# Inputs.net
KiCad netlist of a schematic drawn in Altium Designer
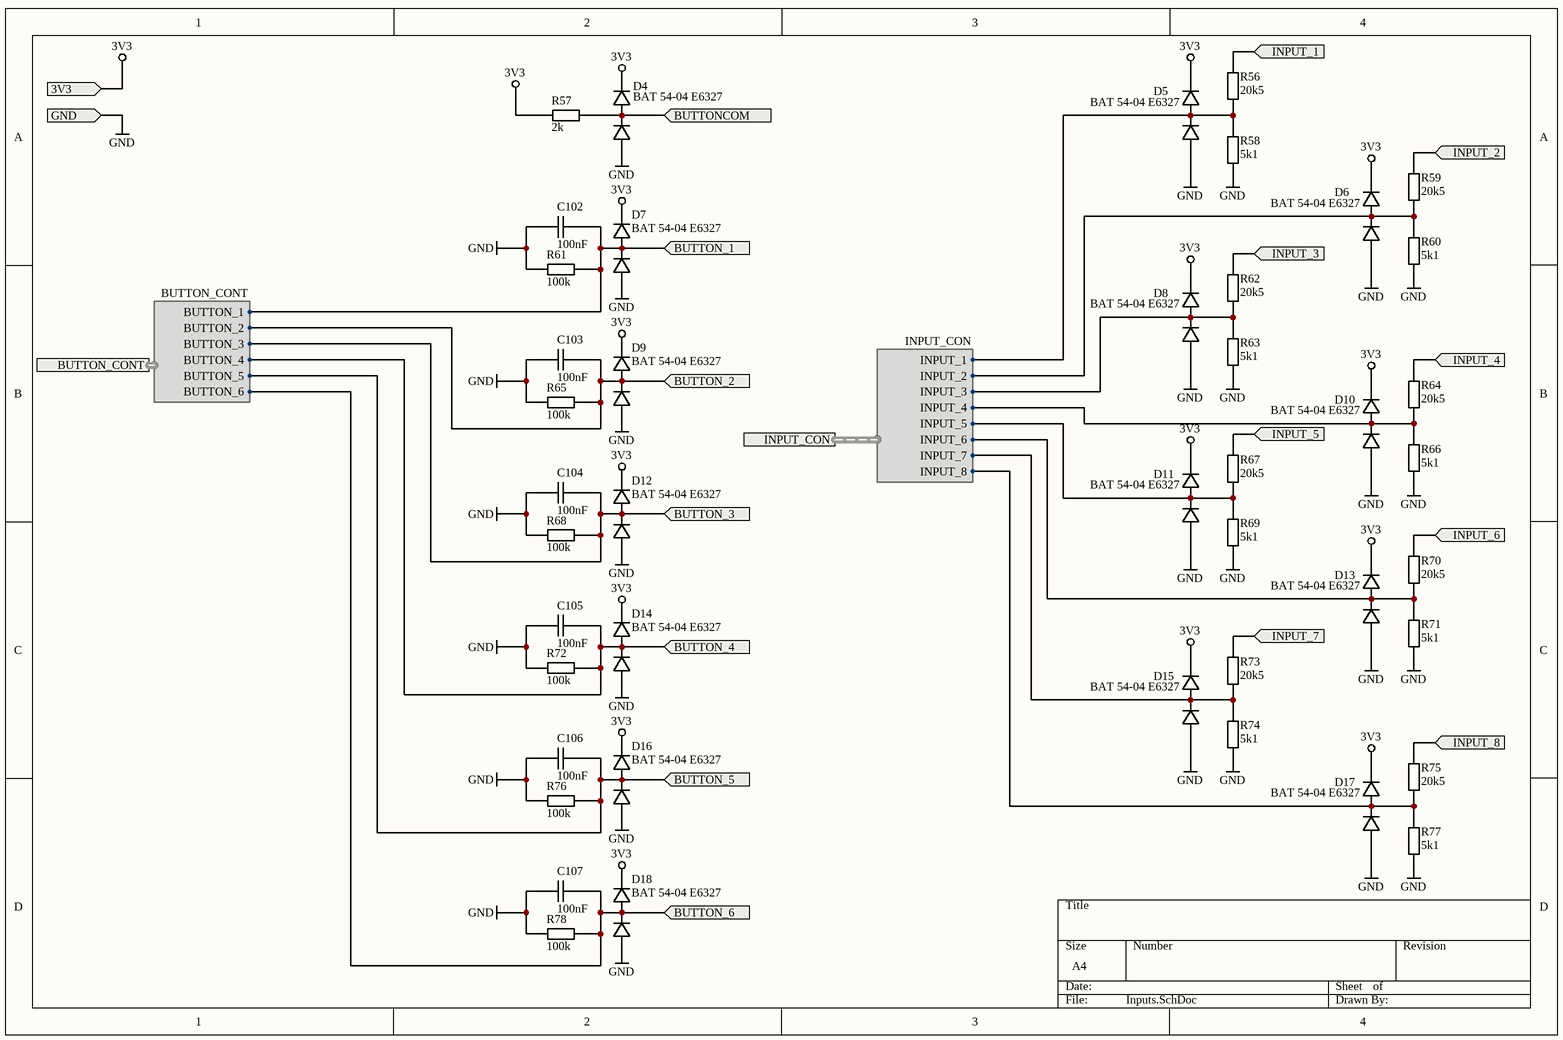
[diagram p0: Inputs.SchDoc]

(export (version "E")
  (design (tool "Eeschema 10.0.6"))
  (components
    (comp (ref "C102")
      (value "100nF")
      (footprint "C_0402")
      (description "100nF 10V 0402 X7R")
      (libsource (lib "SchematicLibrary") (part "C0402C104J8RACAUTO"))
    )
    (comp (ref "C103")
      (value "100nF")
      (footprint "C_0402")
      (description "100nF 10V 0402 X7R")
      (libsource (lib "SchematicLibrary") (part "C0402C104J8RACAUTO"))
    )
    (comp (ref "C104")
      (value "100nF")
      (footprint "C_0402")
      (description "100nF 10V 0402 X7R")
      (libsource (lib "SchematicLibrary") (part "C0402C104J8RACAUTO"))
    )
    (comp (ref "C105")
      (value "100nF")
      (footprint "C_0402")
      (description "100nF 10V 0402 X7R")
      (libsource (lib "SchematicLibrary") (part "C0402C104J8RACAUTO"))
    )
    (comp (ref "C106")
      (value "100nF")
      (footprint "C_0402")
      (description "100nF 10V 0402 X7R")
      (libsource (lib "SchematicLibrary") (part "C0402C104J8RACAUTO"))
    )
    (comp (ref "C107")
      (value "100nF")
      (footprint "C_0402")
      (description "100nF 10V 0402 X7R")
      (libsource (lib "SchematicLibrary") (part "C0402C104J8RACAUTO"))
    )
    (comp (ref "D4")
      (value "BAT 54-04 E6327")
      (footprint "SOT95P240X110-3N")
      (description "Clamping Diode")
      (libsource (lib "SchematicLibrary") (part "BAT 54-04 E6327"))
    )
    (comp (ref "D5")
      (value "BAT 54-04 E6327")
      (footprint "SOT95P240X110-3N")
      (description "Clamping Diode")
      (libsource (lib "SchematicLibrary") (part "BAT 54-04 E6327"))
    )
    (comp (ref "D6")
      (value "BAT 54-04 E6327")
      (footprint "SOT95P240X110-3N")
      (description "Clamping Diode")
      (libsource (lib "SchematicLibrary") (part "BAT 54-04 E6327"))
    )
    (comp (ref "D7")
      (value "BAT 54-04 E6327")
      (footprint "SOT95P240X110-3N")
      (description "Clamping Diode")
      (libsource (lib "SchematicLibrary") (part "BAT 54-04 E6327"))
    )
    (comp (ref "D8")
      (value "BAT 54-04 E6327")
      (footprint "SOT95P240X110-3N")
      (description "Clamping Diode")
      (libsource (lib "SchematicLibrary") (part "BAT 54-04 E6327"))
    )
    (comp (ref "D9")
      (value "BAT 54-04 E6327")
      (footprint "SOT95P240X110-3N")
      (description "Clamping Diode")
      (libsource (lib "SchematicLibrary") (part "BAT 54-04 E6327"))
    )
    (comp (ref "D10")
      (value "BAT 54-04 E6327")
      (footprint "SOT95P240X110-3N")
      (description "Clamping Diode")
      (libsource (lib "SchematicLibrary") (part "BAT 54-04 E6327"))
    )
    (comp (ref "D11")
      (value "BAT 54-04 E6327")
      (footprint "SOT95P240X110-3N")
      (description "Clamping Diode")
      (libsource (lib "SchematicLibrary") (part "BAT 54-04 E6327"))
    )
    (comp (ref "D12")
      (value "BAT 54-04 E6327")
      (footprint "SOT95P240X110-3N")
      (description "Clamping Diode")
      (libsource (lib "SchematicLibrary") (part "BAT 54-04 E6327"))
    )
    (comp (ref "D13")
      (value "BAT 54-04 E6327")
      (footprint "SOT95P240X110-3N")
      (description "Clamping Diode")
      (libsource (lib "SchematicLibrary") (part "BAT 54-04 E6327"))
    )
    (comp (ref "D14")
      (value "BAT 54-04 E6327")
      (footprint "SOT95P240X110-3N")
      (description "Clamping Diode")
      (libsource (lib "SchematicLibrary") (part "BAT 54-04 E6327"))
    )
    (comp (ref "D15")
      (value "BAT 54-04 E6327")
      (footprint "SOT95P240X110-3N")
      (description "Clamping Diode")
      (libsource (lib "SchematicLibrary") (part "BAT 54-04 E6327"))
    )
    (comp (ref "D16")
      (value "BAT 54-04 E6327")
      (footprint "SOT95P240X110-3N")
      (description "Clamping Diode")
      (libsource (lib "SchematicLibrary") (part "BAT 54-04 E6327"))
    )
    (comp (ref "D17")
      (value "BAT 54-04 E6327")
      (footprint "SOT95P240X110-3N")
      (description "Clamping Diode")
      (libsource (lib "SchematicLibrary") (part "BAT 54-04 E6327"))
    )
    (comp (ref "D18")
      (value "BAT 54-04 E6327")
      (footprint "SOT95P240X110-3N")
      (description "Clamping Diode")
      (libsource (lib "SchematicLibrary") (part "BAT 54-04 E6327"))
    )
    (comp (ref "R56")
      (value "20k5")
      (footprint "R_0402")
      (description "20k5 1% 100mW")
      (libsource (lib "SchematicLibrary") (part "ERJ2RKF2052X"))
    )
    (comp (ref "R57")
      (value "2k")
      (footprint "R_0402")
      (description "2k 1% 62.5mW")
      (libsource (lib "SchematicLibrary") (part "AC0402FR-072KL"))
    )
    (comp (ref "R58")
      (value "5k1")
      (footprint "R_0402")
      (description "5k1 1% 100mW")
      (libsource (lib "SchematicLibrary") (part "MP000528"))
    )
    (comp (ref "R59")
      (value "20k5")
      (footprint "R_0402")
      (description "20k5 1% 100mW")
      (libsource (lib "SchematicLibrary") (part "ERJ2RKF2052X"))
    )
    (comp (ref "R60")
      (value "5k1")
      (footprint "R_0402")
      (description "5k1 1% 100mW")
      (libsource (lib "SchematicLibrary") (part "MP000528"))
    )
    (comp (ref "R61")
      (value "100k")
      (footprint "R_0402")
      (description "100k 5% 62.5mW")
      (libsource (lib "SchematicLibrary") (part "CRCW0402100KJNED"))
    )
    (comp (ref "R62")
      (value "20k5")
      (footprint "R_0402")
      (description "20k5 1% 100mW")
      (libsource (lib "SchematicLibrary") (part "ERJ2RKF2052X"))
    )
    (comp (ref "R63")
      (value "5k1")
      (footprint "R_0402")
      (description "5k1 1% 100mW")
      (libsource (lib "SchematicLibrary") (part "MP000528"))
    )
    (comp (ref "R64")
      (value "20k5")
      (footprint "R_0402")
      (description "20k5 1% 100mW")
      (libsource (lib "SchematicLibrary") (part "ERJ2RKF2052X"))
    )
    (comp (ref "R65")
      (value "100k")
      (footprint "R_0402")
      (description "100k 5% 62.5mW")
      (libsource (lib "SchematicLibrary") (part "CRCW0402100KJNED"))
    )
    (comp (ref "R66")
      (value "5k1")
      (footprint "R_0402")
      (description "5k1 1% 100mW")
      (libsource (lib "SchematicLibrary") (part "MP000528"))
    )
    (comp (ref "R67")
      (value "20k5")
      (footprint "R_0402")
      (description "20k5 1% 100mW")
      (libsource (lib "SchematicLibrary") (part "ERJ2RKF2052X"))
    )
    (comp (ref "R68")
      (value "100k")
      (footprint "R_0402")
      (description "100k 5% 62.5mW")
      (libsource (lib "SchematicLibrary") (part "CRCW0402100KJNED"))
    )
    (comp (ref "R69")
      (value "5k1")
      (footprint "R_0402")
      (description "5k1 1% 100mW")
      (libsource (lib "SchematicLibrary") (part "MP000528"))
    )
    (comp (ref "R70")
      (value "20k5")
      (footprint "R_0402")
      (description "20k5 1% 100mW")
      (libsource (lib "SchematicLibrary") (part "ERJ2RKF2052X"))
    )
    (comp (ref "R71")
      (value "5k1")
      (footprint "R_0402")
      (description "5k1 1% 100mW")
      (libsource (lib "SchematicLibrary") (part "MP000528"))
    )
    (comp (ref "R72")
      (value "100k")
      (footprint "R_0402")
      (description "100k 5% 62.5mW")
      (libsource (lib "SchematicLibrary") (part "CRCW0402100KJNED"))
    )
    (comp (ref "R73")
      (value "20k5")
      (footprint "R_0402")
      (description "20k5 1% 100mW")
      (libsource (lib "SchematicLibrary") (part "ERJ2RKF2052X"))
    )
    (comp (ref "R74")
      (value "5k1")
      (footprint "R_0402")
      (description "5k1 1% 100mW")
      (libsource (lib "SchematicLibrary") (part "MP000528"))
    )
    (comp (ref "R75")
      (value "20k5")
      (footprint "R_0402")
      (description "20k5 1% 100mW")
      (libsource (lib "SchematicLibrary") (part "ERJ2RKF2052X"))
    )
    (comp (ref "R76")
      (value "100k")
      (footprint "R_0402")
      (description "100k 5% 62.5mW")
      (libsource (lib "SchematicLibrary") (part "CRCW0402100KJNED"))
    )
    (comp (ref "R77")
      (value "5k1")
      (footprint "R_0402")
      (description "5k1 1% 100mW")
      (libsource (lib "SchematicLibrary") (part "MP000528"))
    )
    (comp (ref "R78")
      (value "100k")
      (footprint "R_0402")
      (description "100k 5% 62.5mW")
      (libsource (lib "SchematicLibrary") (part "CRCW0402100KJNED"))
    )
  )
  (nets
    (net (code "3") (name "/BUTTONCOM") (class "Default")
      (node (ref "D4") (pin "3") (pinfunction "3_3") (pintype "passive"))
      (node (ref "R57") (pin "2") (pinfunction "2_2") (pintype "passive"))
    )
    (net (code "4") (name "/BUTTON_1") (class "Default")
      (node (ref "C102") (pin "2") (pinfunction "2_2") (pintype "passive"))
      (node (ref "D7") (pin "3") (pinfunction "3_3") (pintype "passive"))
      (node (ref "R61") (pin "2") (pinfunction "2_2") (pintype "passive"))
    )
    (net (code "5") (name "/BUTTON_2") (class "Default")
      (node (ref "C103") (pin "2") (pinfunction "2_2") (pintype "passive"))
      (node (ref "D9") (pin "3") (pinfunction "3_3") (pintype "passive"))
      (node (ref "R65") (pin "2") (pinfunction "2_2") (pintype "passive"))
    )
    (net (code "6") (name "/BUTTON_3") (class "Default")
      (node (ref "C104") (pin "2") (pinfunction "2_2") (pintype "passive"))
      (node (ref "D12") (pin "3") (pinfunction "3_3") (pintype "passive"))
      (node (ref "R68") (pin "2") (pinfunction "2_2") (pintype "passive"))
    )
    (net (code "7") (name "/BUTTON_4") (class "Default")
      (node (ref "C105") (pin "2") (pinfunction "2_2") (pintype "passive"))
      (node (ref "D14") (pin "3") (pinfunction "3_3") (pintype "passive"))
      (node (ref "R72") (pin "2") (pinfunction "2_2") (pintype "passive"))
    )
    (net (code "8") (name "/BUTTON_5") (class "Default")
      (node (ref "C106") (pin "2") (pinfunction "2_2") (pintype "passive"))
      (node (ref "D16") (pin "3") (pinfunction "3_3") (pintype "passive"))
      (node (ref "R76") (pin "2") (pinfunction "2_2") (pintype "passive"))
    )
    (net (code "9") (name "/BUTTON_6") (class "Default")
      (node (ref "C107") (pin "2") (pinfunction "2_2") (pintype "passive"))
      (node (ref "D18") (pin "3") (pinfunction "3_3") (pintype "passive"))
      (node (ref "R78") (pin "2") (pinfunction "2_2") (pintype "passive"))
    )
    (net (code "10") (name "/INPUT_1") (class "Default")
      (node (ref "R56") (pin "2") (pinfunction "2_2") (pintype "passive"))
    )
    (net (code "11") (name "/INPUT_2") (class "Default")
      (node (ref "R59") (pin "2") (pinfunction "2_2") (pintype "passive"))
    )
    (net (code "12") (name "/INPUT_3") (class "Default")
      (node (ref "R62") (pin "2") (pinfunction "2_2") (pintype "passive"))
    )
    (net (code "13") (name "/INPUT_4") (class "Default")
      (node (ref "R64") (pin "2") (pinfunction "2_2") (pintype "passive"))
    )
    (net (code "14") (name "/INPUT_5") (class "Default")
      (node (ref "R67") (pin "2") (pinfunction "2_2") (pintype "passive"))
    )
    (net (code "15") (name "/INPUT_6") (class "Default")
      (node (ref "R70") (pin "2") (pinfunction "2_2") (pintype "passive"))
    )
    (net (code "16") (name "/INPUT_7") (class "Default")
      (node (ref "R73") (pin "2") (pinfunction "2_2") (pintype "passive"))
    )
    (net (code "17") (name "/INPUT_8") (class "Default")
      (node (ref "R75") (pin "2") (pinfunction "2_2") (pintype "passive"))
    )
    (net (code "20") (name "3V3") (class "Default")
      (node (ref "D10") (pin "2") (pinfunction "2_2") (pintype "passive"))
      (node (ref "D11") (pin "2") (pinfunction "2_2") (pintype "passive"))
      (node (ref "D12") (pin "2") (pinfunction "2_2") (pintype "passive"))
      (node (ref "D13") (pin "2") (pinfunction "2_2") (pintype "passive"))
      (node (ref "D14") (pin "2") (pinfunction "2_2") (pintype "passive"))
      (node (ref "D15") (pin "2") (pinfunction "2_2") (pintype "passive"))
      (node (ref "D16") (pin "2") (pinfunction "2_2") (pintype "passive"))
      (node (ref "D17") (pin "2") (pinfunction "2_2") (pintype "passive"))
      (node (ref "D18") (pin "2") (pinfunction "2_2") (pintype "passive"))
      (node (ref "D4") (pin "2") (pinfunction "2_2") (pintype "passive"))
      (node (ref "D5") (pin "2") (pinfunction "2_2") (pintype "passive"))
      (node (ref "D6") (pin "2") (pinfunction "2_2") (pintype "passive"))
      (node (ref "D7") (pin "2") (pinfunction "2_2") (pintype "passive"))
      (node (ref "D8") (pin "2") (pinfunction "2_2") (pintype "passive"))
      (node (ref "D9") (pin "2") (pinfunction "2_2") (pintype "passive"))
      (node (ref "R57") (pin "1") (pinfunction "1_1") (pintype "passive"))
    )
    (net (code "21") (name "GND") (class "Default")
      (node (ref "C102") (pin "1") (pinfunction "1_1") (pintype "passive"))
      (node (ref "C103") (pin "1") (pinfunction "1_1") (pintype "passive"))
      (node (ref "C104") (pin "1") (pinfunction "1_1") (pintype "passive"))
      (node (ref "C105") (pin "1") (pinfunction "1_1") (pintype "passive"))
      (node (ref "C106") (pin "1") (pinfunction "1_1") (pintype "passive"))
      (node (ref "C107") (pin "1") (pinfunction "1_1") (pintype "passive"))
      (node (ref "D10") (pin "1") (pinfunction "1_1") (pintype "passive"))
      (node (ref "D11") (pin "1") (pinfunction "1_1") (pintype "passive"))
      (node (ref "D12") (pin "1") (pinfunction "1_1") (pintype "passive"))
      (node (ref "D13") (pin "1") (pinfunction "1_1") (pintype "passive"))
      (node (ref "D14") (pin "1") (pinfunction "1_1") (pintype "passive"))
      (node (ref "D15") (pin "1") (pinfunction "1_1") (pintype "passive"))
      (node (ref "D16") (pin "1") (pinfunction "1_1") (pintype "passive"))
      (node (ref "D17") (pin "1") (pinfunction "1_1") (pintype "passive"))
      (node (ref "D18") (pin "1") (pinfunction "1_1") (pintype "passive"))
      (node (ref "D4") (pin "1") (pinfunction "1_1") (pintype "passive"))
      (node (ref "D5") (pin "1") (pinfunction "1_1") (pintype "passive"))
      (node (ref "D6") (pin "1") (pinfunction "1_1") (pintype "passive"))
      (node (ref "D7") (pin "1") (pinfunction "1_1") (pintype "passive"))
      (node (ref "D8") (pin "1") (pinfunction "1_1") (pintype "passive"))
      (node (ref "D9") (pin "1") (pinfunction "1_1") (pintype "passive"))
      (node (ref "R58") (pin "1") (pinfunction "1_1") (pintype "passive"))
      (node (ref "R60") (pin "1") (pinfunction "1_1") (pintype "passive"))
      (node (ref "R61") (pin "1") (pinfunction "1_1") (pintype "passive"))
      (node (ref "R63") (pin "1") (pinfunction "1_1") (pintype "passive"))
      (node (ref "R65") (pin "1") (pinfunction "1_1") (pintype "passive"))
      (node (ref "R66") (pin "1") (pinfunction "1_1") (pintype "passive"))
      (node (ref "R68") (pin "1") (pinfunction "1_1") (pintype "passive"))
      (node (ref "R69") (pin "1") (pinfunction "1_1") (pintype "passive"))
      (node (ref "R71") (pin "1") (pinfunction "1_1") (pintype "passive"))
      (node (ref "R72") (pin "1") (pinfunction "1_1") (pintype "passive"))
      (node (ref "R74") (pin "1") (pinfunction "1_1") (pintype "passive"))
      (node (ref "R76") (pin "1") (pinfunction "1_1") (pintype "passive"))
      (node (ref "R77") (pin "1") (pinfunction "1_1") (pintype "passive"))
      (node (ref "R78") (pin "1") (pinfunction "1_1") (pintype "passive"))
    )
    (net (code "22") (name "Net-(D5-Pad3)") (class "Default")
      (node (ref "D5") (pin "3") (pinfunction "3_3") (pintype "passive"))
      (node (ref "R56") (pin "1") (pinfunction "1_1") (pintype "passive"))
      (node (ref "R58") (pin "2") (pinfunction "2_2") (pintype "passive"))
    )
    (net (code "23") (name "Net-(D6-Pad3)") (class "Default")
      (node (ref "D6") (pin "3") (pinfunction "3_3") (pintype "passive"))
      (node (ref "R59") (pin "1") (pinfunction "1_1") (pintype "passive"))
      (node (ref "R60") (pin "2") (pinfunction "2_2") (pintype "passive"))
    )
    (net (code "24") (name "Net-(D8-Pad3)") (class "Default")
      (node (ref "D8") (pin "3") (pinfunction "3_3") (pintype "passive"))
      (node (ref "R62") (pin "1") (pinfunction "1_1") (pintype "passive"))
      (node (ref "R63") (pin "2") (pinfunction "2_2") (pintype "passive"))
    )
    (net (code "25") (name "Net-(D10-Pad3)") (class "Default")
      (node (ref "D10") (pin "3") (pinfunction "3_3") (pintype "passive"))
      (node (ref "R64") (pin "1") (pinfunction "1_1") (pintype "passive"))
      (node (ref "R66") (pin "2") (pinfunction "2_2") (pintype "passive"))
    )
    (net (code "26") (name "Net-(D11-Pad3)") (class "Default")
      (node (ref "D11") (pin "3") (pinfunction "3_3") (pintype "passive"))
      (node (ref "R67") (pin "1") (pinfunction "1_1") (pintype "passive"))
      (node (ref "R69") (pin "2") (pinfunction "2_2") (pintype "passive"))
    )
    (net (code "27") (name "Net-(D13-Pad3)") (class "Default")
      (node (ref "D13") (pin "3") (pinfunction "3_3") (pintype "passive"))
      (node (ref "R70") (pin "1") (pinfunction "1_1") (pintype "passive"))
      (node (ref "R71") (pin "2") (pinfunction "2_2") (pintype "passive"))
    )
    (net (code "28") (name "Net-(D15-Pad3)") (class "Default")
      (node (ref "D15") (pin "3") (pinfunction "3_3") (pintype "passive"))
      (node (ref "R73") (pin "1") (pinfunction "1_1") (pintype "passive"))
      (node (ref "R74") (pin "2") (pinfunction "2_2") (pintype "passive"))
    )
    (net (code "29") (name "Net-(D17-Pad3)") (class "Default")
      (node (ref "D17") (pin "3") (pinfunction "3_3") (pintype "passive"))
      (node (ref "R75") (pin "1") (pinfunction "1_1") (pintype "passive"))
      (node (ref "R77") (pin "2") (pinfunction "2_2") (pintype "passive"))
    )
  )
)
